# Sheet1.net
KiCad netlist of a schematic drawn in Altium Designer
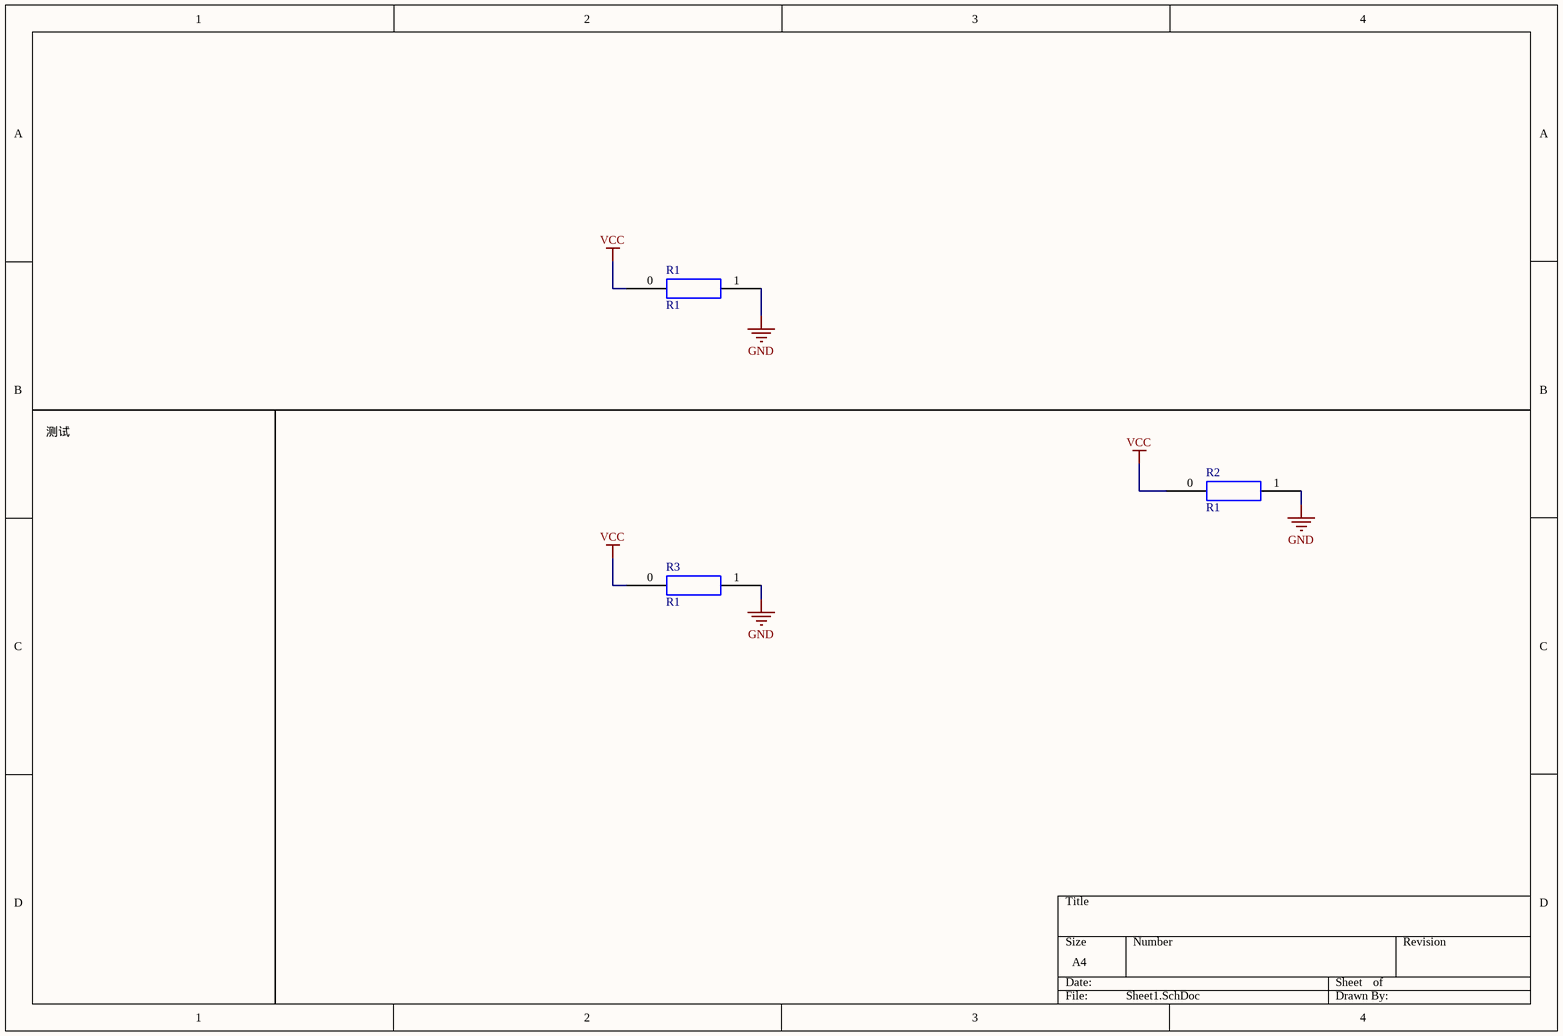
[diagram p0: Sheet1.SchDoc]

(export (version "E")
  (design (tool "Eeschema 10.0.6"))
  (components
    (comp (ref "R1") (value "R1") (libsource (lib "Schlib1") (part "R1")))
    (comp (ref "R2") (value "R1") (libsource (lib "Schlib1") (part "R1")))
    (comp (ref "R3") (value "R1") (libsource (lib "Schlib1") (part "R1")))
  )
  (nets
    (net (code "1") (name "GND") (class "Default")
      (node (ref "R1") (pin "1") (pinfunction "1_1") (pintype "passive"))
      (node (ref "R2") (pin "1") (pinfunction "1_1") (pintype "passive"))
      (node (ref "R3") (pin "1") (pinfunction "1_1") (pintype "passive"))
    )
    (net (code "2") (name "VCC") (class "Default")
      (node (ref "R1") (pin "0") (pinfunction "0_0") (pintype "passive"))
      (node (ref "R2") (pin "0") (pinfunction "0_0") (pintype "passive"))
      (node (ref "R3") (pin "0") (pinfunction "0_0") (pintype "passive"))
    )
  )
)
